# VU_LED.net
KiCad netlist of a schematic drawn in Altium Designer
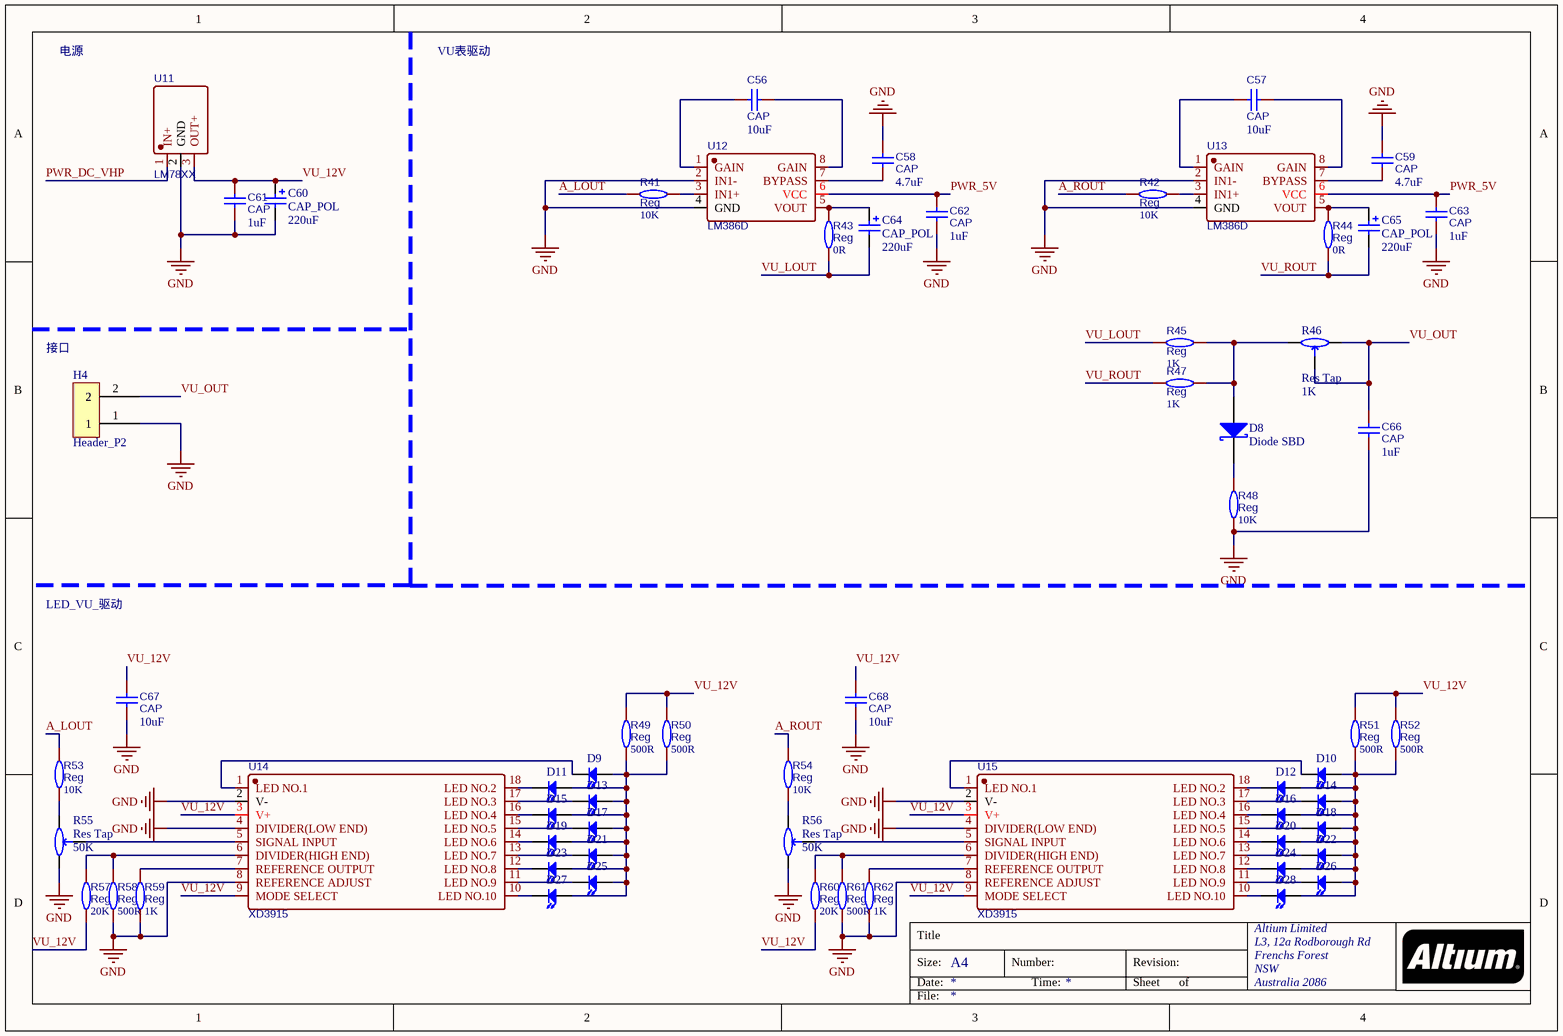
[diagram p0: VU_LED.SchDoc]

(export (version "E")
  (design (tool "Eeschema 10.0.6"))
  (components
    (comp (ref "C56")
      (value "CAP")
      (footprint "C0603")
      (description "Cap")
      (fields
        (field (name "BOM_SUPPLIER PART") "C302008")
        (field (name "BOM_MANUFACTURER PART") "0603B103K101CT")
        (field (name "ALTIUM_VALUE") "10uF")
        (field (name "CONTRIBUTOR") "LCSC")
      )
      (libsource (lib "Levent_lib") (part "CAP"))
    )
    (comp (ref "C57")
      (value "CAP")
      (footprint "C0603")
      (description "Cap")
      (fields
        (field (name "BOM_SUPPLIER PART") "C302008")
        (field (name "BOM_MANUFACTURER PART") "0603B103K101CT")
        (field (name "ALTIUM_VALUE") "10uF")
        (field (name "CONTRIBUTOR") "LCSC")
      )
      (libsource (lib "Levent_lib") (part "CAP"))
    )
    (comp (ref "C58")
      (value "CAP")
      (footprint "C0603")
      (description "Cap")
      (fields
        (field (name "BOM_SUPPLIER PART") "C302008")
        (field (name "BOM_MANUFACTURER PART") "0603B103K101CT")
        (field (name "ALTIUM_VALUE") "4.7uF")
        (field (name "CONTRIBUTOR") "LCSC")
      )
      (libsource (lib "Levent_lib") (part "CAP"))
    )
    (comp (ref "C59")
      (value "CAP")
      (footprint "C0603")
      (description "Cap")
      (fields
        (field (name "BOM_SUPPLIER PART") "C302008")
        (field (name "BOM_MANUFACTURER PART") "0603B103K101CT")
        (field (name "ALTIUM_VALUE") "4.7uF")
        (field (name "CONTRIBUTOR") "LCSC")
      )
      (libsource (lib "Levent_lib") (part "CAP"))
    )
    (comp (ref "C60")
      (value "CAP_POL")
      (footprint "CAP_SMD_6.3mm")
      (description "极性电容")
      (fields (field (name "ALTIUM_VALUE") "220uF"))
      (libsource (lib "Levent_lib") (part "CAP_POL"))
    )
    (comp (ref "C61")
      (value "CAP")
      (footprint "C0603")
      (description "Cap")
      (fields
        (field (name "BOM_SUPPLIER PART") "C302008")
        (field (name "BOM_MANUFACTURER PART") "0603B103K101CT")
        (field (name "ALTIUM_VALUE") "1uF")
        (field (name "CONTRIBUTOR") "LCSC")
      )
      (libsource (lib "Levent_lib") (part "CAP"))
    )
    (comp (ref "C62")
      (value "CAP")
      (footprint "C0603")
      (description "Cap")
      (fields
        (field (name "BOM_SUPPLIER PART") "C302008")
        (field (name "BOM_MANUFACTURER PART") "0603B103K101CT")
        (field (name "ALTIUM_VALUE") "1uF")
        (field (name "CONTRIBUTOR") "LCSC")
      )
      (libsource (lib "Levent_lib") (part "CAP"))
    )
    (comp (ref "C63")
      (value "CAP")
      (footprint "C0603")
      (description "Cap")
      (fields
        (field (name "BOM_SUPPLIER PART") "C302008")
        (field (name "BOM_MANUFACTURER PART") "0603B103K101CT")
        (field (name "ALTIUM_VALUE") "1uF")
        (field (name "CONTRIBUTOR") "LCSC")
      )
      (libsource (lib "Levent_lib") (part "CAP"))
    )
    (comp (ref "C64")
      (value "CAP_POL")
      (footprint "CAP_SMD_6.3mm")
      (description "极性电容")
      (fields (field (name "ALTIUM_VALUE") "220uF"))
      (libsource (lib "Levent_lib") (part "CAP_POL"))
    )
    (comp (ref "C65")
      (value "CAP_POL")
      (footprint "CAP_SMD_6.3mm")
      (description "极性电容")
      (fields (field (name "ALTIUM_VALUE") "220uF"))
      (libsource (lib "Levent_lib") (part "CAP_POL"))
    )
    (comp (ref "C66")
      (value "CAP")
      (footprint "C0603")
      (description "Cap")
      (fields
        (field (name "BOM_SUPPLIER PART") "C302008")
        (field (name "BOM_MANUFACTURER PART") "0603B103K101CT")
        (field (name "ALTIUM_VALUE") "1uF")
        (field (name "CONTRIBUTOR") "LCSC")
      )
      (libsource (lib "Levent_lib") (part "CAP"))
    )
    (comp (ref "C67")
      (value "CAP")
      (footprint "C0603")
      (description "Cap")
      (fields
        (field (name "BOM_SUPPLIER PART") "C302008")
        (field (name "BOM_MANUFACTURER PART") "0603B103K101CT")
        (field (name "ALTIUM_VALUE") "10uF")
        (field (name "CONTRIBUTOR") "LCSC")
      )
      (libsource (lib "Levent_lib") (part "CAP"))
    )
    (comp (ref "C68")
      (value "CAP")
      (footprint "C0603")
      (description "Cap")
      (fields
        (field (name "BOM_SUPPLIER PART") "C302008")
        (field (name "BOM_MANUFACTURER PART") "0603B103K101CT")
        (field (name "ALTIUM_VALUE") "10uF")
        (field (name "CONTRIBUTOR") "LCSC")
      )
      (libsource (lib "Levent_lib") (part "CAP"))
    )
    (comp (ref "D8")
      (value "Diode SBD")
      (footprint "SMA_L4.3")
      (description "Schottky Rectifier")
      (fields (field (name "PUBLISHER") "Altium Limited"))
      (libsource (lib "Levent_lib") (part "Diode SBD"))
    )
    (comp (ref "D9")
      (value "LED")
      (footprint "LED0603_Side")
      (fields (field (name "PUBLISHER") "Altium Limited"))
      (libsource (lib "Levent_lib") (part "LED0"))
    )
    (comp (ref "D10")
      (value "LED")
      (footprint "LED0603_Side")
      (fields (field (name "PUBLISHER") "Altium Limited"))
      (libsource (lib "Levent_lib") (part "LED0"))
    )
    (comp (ref "D11")
      (value "LED")
      (footprint "LED0603_Side")
      (fields (field (name "PUBLISHER") "Altium Limited"))
      (libsource (lib "Levent_lib") (part "LED0"))
    )
    (comp (ref "D12")
      (value "LED")
      (footprint "LED0603_Side")
      (fields (field (name "PUBLISHER") "Altium Limited"))
      (libsource (lib "Levent_lib") (part "LED0"))
    )
    (comp (ref "D13")
      (value "LED")
      (footprint "LED0603_Side")
      (fields (field (name "PUBLISHER") "Altium Limited"))
      (libsource (lib "Levent_lib") (part "LED0"))
    )
    (comp (ref "D14")
      (value "LED")
      (footprint "LED0603_Side")
      (fields (field (name "PUBLISHER") "Altium Limited"))
      (libsource (lib "Levent_lib") (part "LED0"))
    )
    (comp (ref "D15")
      (value "LED")
      (footprint "LED0603_Side")
      (fields (field (name "PUBLISHER") "Altium Limited"))
      (libsource (lib "Levent_lib") (part "LED0"))
    )
    (comp (ref "D16")
      (value "LED")
      (footprint "LED0603_Side")
      (fields (field (name "PUBLISHER") "Altium Limited"))
      (libsource (lib "Levent_lib") (part "LED0"))
    )
    (comp (ref "D17")
      (value "LED")
      (footprint "LED0603_Side")
      (fields (field (name "PUBLISHER") "Altium Limited"))
      (libsource (lib "Levent_lib") (part "LED0"))
    )
    (comp (ref "D18")
      (value "LED")
      (footprint "LED0603_Side")
      (fields (field (name "PUBLISHER") "Altium Limited"))
      (libsource (lib "Levent_lib") (part "LED0"))
    )
    (comp (ref "D19")
      (value "LED")
      (footprint "LED0603_Side")
      (fields (field (name "PUBLISHER") "Altium Limited"))
      (libsource (lib "Levent_lib") (part "LED0"))
    )
    (comp (ref "D20")
      (value "LED")
      (footprint "LED0603_Side")
      (fields (field (name "PUBLISHER") "Altium Limited"))
      (libsource (lib "Levent_lib") (part "LED0"))
    )
    (comp (ref "D21")
      (value "LED")
      (footprint "LED0603_Side")
      (fields (field (name "PUBLISHER") "Altium Limited"))
      (libsource (lib "Levent_lib") (part "LED0"))
    )
    (comp (ref "D22")
      (value "LED")
      (footprint "LED0603_Side")
      (fields (field (name "PUBLISHER") "Altium Limited"))
      (libsource (lib "Levent_lib") (part "LED0"))
    )
    (comp (ref "D23")
      (value "LED")
      (footprint "LED0603_Side")
      (fields (field (name "PUBLISHER") "Altium Limited"))
      (libsource (lib "Levent_lib") (part "LED0"))
    )
    (comp (ref "D24")
      (value "LED")
      (footprint "LED0603_Side")
      (fields (field (name "PUBLISHER") "Altium Limited"))
      (libsource (lib "Levent_lib") (part "LED0"))
    )
    (comp (ref "D25")
      (value "LED")
      (footprint "LED0603_Side")
      (fields (field (name "PUBLISHER") "Altium Limited"))
      (libsource (lib "Levent_lib") (part "LED0"))
    )
    (comp (ref "D26")
      (value "LED")
      (footprint "LED0603_Side")
      (fields (field (name "PUBLISHER") "Altium Limited"))
      (libsource (lib "Levent_lib") (part "LED0"))
    )
    (comp (ref "D27")
      (value "LED")
      (footprint "LED0603_Side")
      (fields (field (name "PUBLISHER") "Altium Limited"))
      (libsource (lib "Levent_lib") (part "LED0"))
    )
    (comp (ref "D28")
      (value "LED")
      (footprint "LED0603_Side")
      (fields (field (name "PUBLISHER") "Altium Limited"))
      (libsource (lib "Levent_lib") (part "LED0"))
    )
    (comp (ref "H4")
      (value "Header_P2")
      (footprint "H_2.54_P2")
      (description "2Pin排针")
      (libsource (lib "Levent_lib") (part "Header_P2"))
    )
    (comp (ref "R41")
      (value "Reg")
      (footprint "R0603")
      (description "电阻")
      (fields
        (field (name "BOM_SUPPLIER PART") "C465721")
        (field (name "BOM_MANUFACTURER PART") "AR03BTCX1002A")
        (field (name "ALTIUM_VALUE") "10K")
        (field (name "CONTRIBUTOR") "LCSC")
      )
      (libsource (lib "Levent_lib") (part "Res"))
    )
    (comp (ref "R42")
      (value "Reg")
      (footprint "R0603")
      (description "电阻")
      (fields
        (field (name "BOM_SUPPLIER PART") "C465721")
        (field (name "BOM_MANUFACTURER PART") "AR03BTCX1002A")
        (field (name "ALTIUM_VALUE") "10K")
        (field (name "CONTRIBUTOR") "LCSC")
      )
      (libsource (lib "Levent_lib") (part "Res"))
    )
    (comp (ref "R43")
      (value "Reg")
      (footprint "R0603")
      (description "电阻")
      (fields
        (field (name "BOM_SUPPLIER PART") "C465721")
        (field (name "BOM_MANUFACTURER PART") "AR03BTCX1002A")
        (field (name "ALTIUM_VALUE") "0R")
        (field (name "CONTRIBUTOR") "LCSC")
      )
      (libsource (lib "Levent_lib") (part "Res"))
    )
    (comp (ref "R44")
      (value "Reg")
      (footprint "R0603")
      (description "电阻")
      (fields
        (field (name "BOM_SUPPLIER PART") "C465721")
        (field (name "BOM_MANUFACTURER PART") "AR03BTCX1002A")
        (field (name "ALTIUM_VALUE") "0R")
        (field (name "CONTRIBUTOR") "LCSC")
      )
      (libsource (lib "Levent_lib") (part "Res"))
    )
    (comp (ref "R45")
      (value "Reg")
      (footprint "R0603")
      (description "电阻")
      (fields
        (field (name "BOM_SUPPLIER PART") "C465721")
        (field (name "BOM_MANUFACTURER PART") "AR03BTCX1002A")
        (field (name "ALTIUM_VALUE") "1K")
        (field (name "CONTRIBUTOR") "LCSC")
      )
      (libsource (lib "Levent_lib") (part "Res"))
    )
    (comp (ref "R46")
      (value "Res Tap")
      (footprint "RES_TAP_HOR")
      (description "可调电阻")
      (fields (field (name "ALTIUM_VALUE") "1K") (field (name "PUBLISHER") "Altium Limited"))
      (libsource (lib "Levent_lib") (part "Res Tap"))
    )
    (comp (ref "R47")
      (value "Reg")
      (footprint "R0603")
      (description "电阻")
      (fields
        (field (name "BOM_SUPPLIER PART") "C465721")
        (field (name "BOM_MANUFACTURER PART") "AR03BTCX1002A")
        (field (name "ALTIUM_VALUE") "1K")
        (field (name "CONTRIBUTOR") "LCSC")
      )
      (libsource (lib "Levent_lib") (part "Res"))
    )
    (comp (ref "R48")
      (value "Reg")
      (footprint "R0603")
      (description "电阻")
      (fields
        (field (name "BOM_SUPPLIER PART") "C465721")
        (field (name "BOM_MANUFACTURER PART") "AR03BTCX1002A")
        (field (name "ALTIUM_VALUE") "10K")
        (field (name "CONTRIBUTOR") "LCSC")
      )
      (libsource (lib "Levent_lib") (part "Res"))
    )
    (comp (ref "R49")
      (value "Reg")
      (footprint "R0603")
      (description "电阻")
      (fields
        (field (name "BOM_SUPPLIER PART") "C465721")
        (field (name "BOM_MANUFACTURER PART") "AR03BTCX1002A")
        (field (name "ALTIUM_VALUE") "500R")
        (field (name "CONTRIBUTOR") "LCSC")
      )
      (libsource (lib "Levent_lib") (part "Res"))
    )
    (comp (ref "R50")
      (value "Reg")
      (footprint "R0603")
      (description "电阻")
      (fields
        (field (name "BOM_SUPPLIER PART") "C465721")
        (field (name "BOM_MANUFACTURER PART") "AR03BTCX1002A")
        (field (name "ALTIUM_VALUE") "500R")
        (field (name "CONTRIBUTOR") "LCSC")
      )
      (libsource (lib "Levent_lib") (part "Res"))
    )
    (comp (ref "R51")
      (value "Reg")
      (footprint "R0603")
      (description "电阻")
      (fields
        (field (name "BOM_SUPPLIER PART") "C465721")
        (field (name "BOM_MANUFACTURER PART") "AR03BTCX1002A")
        (field (name "ALTIUM_VALUE") "500R")
        (field (name "CONTRIBUTOR") "LCSC")
      )
      (libsource (lib "Levent_lib") (part "Res"))
    )
    (comp (ref "R52")
      (value "Reg")
      (footprint "R0603")
      (description "电阻")
      (fields
        (field (name "BOM_SUPPLIER PART") "C465721")
        (field (name "BOM_MANUFACTURER PART") "AR03BTCX1002A")
        (field (name "ALTIUM_VALUE") "500R")
        (field (name "CONTRIBUTOR") "LCSC")
      )
      (libsource (lib "Levent_lib") (part "Res"))
    )
    (comp (ref "R53")
      (value "Reg")
      (footprint "R0603")
      (description "电阻")
      (fields
        (field (name "BOM_SUPPLIER PART") "C465721")
        (field (name "BOM_MANUFACTURER PART") "AR03BTCX1002A")
        (field (name "ALTIUM_VALUE") "10K")
        (field (name "CONTRIBUTOR") "LCSC")
      )
      (libsource (lib "Levent_lib") (part "Res"))
    )
    (comp (ref "R54")
      (value "Reg")
      (footprint "R0603")
      (description "电阻")
      (fields
        (field (name "BOM_SUPPLIER PART") "C465721")
        (field (name "BOM_MANUFACTURER PART") "AR03BTCX1002A")
        (field (name "ALTIUM_VALUE") "10K")
        (field (name "CONTRIBUTOR") "LCSC")
      )
      (libsource (lib "Levent_lib") (part "Res"))
    )
    (comp (ref "R55")
      (value "Res Tap")
      (footprint "RES_TAP_HOR")
      (description "可调电阻")
      (fields (field (name "ALTIUM_VALUE") "50K") (field (name "PUBLISHER") "Altium Limited"))
      (libsource (lib "Levent_lib") (part "Res Tap"))
    )
    (comp (ref "R56")
      (value "Res Tap")
      (footprint "RES_TAP_HOR")
      (description "可调电阻")
      (fields (field (name "ALTIUM_VALUE") "50K") (field (name "PUBLISHER") "Altium Limited"))
      (libsource (lib "Levent_lib") (part "Res Tap"))
    )
    (comp (ref "R57")
      (value "Reg")
      (footprint "R0603")
      (description "电阻")
      (fields
        (field (name "BOM_SUPPLIER PART") "C465721")
        (field (name "BOM_MANUFACTURER PART") "AR03BTCX1002A")
        (field (name "ALTIUM_VALUE") "20K")
        (field (name "CONTRIBUTOR") "LCSC")
      )
      (libsource (lib "Levent_lib") (part "Res"))
    )
    (comp (ref "R58")
      (value "Reg")
      (footprint "R0603")
      (description "电阻")
      (fields
        (field (name "BOM_SUPPLIER PART") "C465721")
        (field (name "BOM_MANUFACTURER PART") "AR03BTCX1002A")
        (field (name "ALTIUM_VALUE") "500R")
        (field (name "CONTRIBUTOR") "LCSC")
      )
      (libsource (lib "Levent_lib") (part "Res"))
    )
    (comp (ref "R59")
      (value "Reg")
      (footprint "R0603")
      (description "电阻")
      (fields
        (field (name "BOM_SUPPLIER PART") "C465721")
        (field (name "BOM_MANUFACTURER PART") "AR03BTCX1002A")
        (field (name "ALTIUM_VALUE") "1K")
        (field (name "CONTRIBUTOR") "LCSC")
      )
      (libsource (lib "Levent_lib") (part "Res"))
    )
    (comp (ref "R60")
      (value "Reg")
      (footprint "R0603")
      (description "电阻")
      (fields
        (field (name "BOM_SUPPLIER PART") "C465721")
        (field (name "BOM_MANUFACTURER PART") "AR03BTCX1002A")
        (field (name "ALTIUM_VALUE") "20K")
        (field (name "CONTRIBUTOR") "LCSC")
      )
      (libsource (lib "Levent_lib") (part "Res"))
    )
    (comp (ref "R61")
      (value "Reg")
      (footprint "R0603")
      (description "电阻")
      (fields
        (field (name "BOM_SUPPLIER PART") "C465721")
        (field (name "BOM_MANUFACTURER PART") "AR03BTCX1002A")
        (field (name "ALTIUM_VALUE") "500R")
        (field (name "CONTRIBUTOR") "LCSC")
      )
      (libsource (lib "Levent_lib") (part "Res"))
    )
    (comp (ref "R62")
      (value "Reg")
      (footprint "R0603")
      (description "电阻")
      (fields
        (field (name "BOM_SUPPLIER PART") "C465721")
        (field (name "BOM_MANUFACTURER PART") "AR03BTCX1002A")
        (field (name "ALTIUM_VALUE") "1K")
        (field (name "CONTRIBUTOR") "LCSC")
      )
      (libsource (lib "Levent_lib") (part "Res"))
    )
    (comp (ref "U11")
      (value "LM78XX")
      (footprint "TO-220-3_2.54_HOR")
      (description "三端稳压(正电压)")
      (fields
        (field (name "BOM_SUPPLIER PART") "C2902509")
        (field (name "BOM_MANUFACTURER PART") "LM7812T")
        (field (name "CONTRIBUTOR") "LCSC")
      )
      (libsource (lib "Levent_lib") (part "LM78XX"))
    )
    (comp (ref "U12")
      (value "LM386D")
      (footprint "SOP-8")
      (description "LM386")
      (fields (field (name "BOM_SUPPLIER PART") "C510560") (field (name "CONTRIBUTOR") "LCSC"))
      (libsource (lib "Levent_lib") (part "LM386D"))
    )
    (comp (ref "U13")
      (value "LM386D")
      (footprint "SOP-8")
      (description "LM386")
      (fields (field (name "BOM_SUPPLIER PART") "C510560") (field (name "CONTRIBUTOR") "LCSC"))
      (libsource (lib "Levent_lib") (part "LM386D"))
    )
    (comp (ref "U14")
      (value "XD3915")
      (footprint "DIP-18")
      (description "电平指示")
      (fields (field (name "BOM_SUPPLIER PART") "C609778") (field (name "CONTRIBUTOR") "LCSC"))
      (libsource (lib "Levent_lib") (part "LM3915"))
    )
    (comp (ref "U15")
      (value "XD3915")
      (footprint "DIP-18")
      (description "电平指示")
      (fields (field (name "BOM_SUPPLIER PART") "C609778") (field (name "CONTRIBUTOR") "LCSC"))
      (libsource (lib "Levent_lib") (part "LM3915"))
    )
  )
  (nets
    (net (code "1") (name "/A_LOUT") (class "Default")
      (node (ref "R41") (pin "2") (pinfunction "2_2") (pintype "passive"))
      (node (ref "R53") (pin "2") (pinfunction "2_2") (pintype "passive"))
    )
    (net (code "2") (name "/A_ROUT") (class "Default")
      (node (ref "R42") (pin "2") (pinfunction "2_2") (pintype "passive"))
      (node (ref "R54") (pin "2") (pinfunction "2_2") (pintype "passive"))
    )
    (net (code "3") (name "/PWR_5V") (class "Default")
      (node (ref "C62") (pin "1") (pinfunction "1_1") (pintype "passive"))
      (node (ref "C63") (pin "1") (pinfunction "1_1") (pintype "passive"))
      (node (ref "U12") (pin "6") (pinfunction "VCC_6") (pintype "passive"))
      (node (ref "U13") (pin "6") (pinfunction "VCC_6") (pintype "passive"))
    )
    (net (code "4") (name "/PWR_DC_VHP") (class "Default")
      (node (ref "U11") (pin "1") (pinfunction "IN+_1") (pintype "passive"))
    )
    (net (code "5") (name "/VU_12V") (class "Default")
      (node (ref "C60") (pin "1") (pinfunction "1_1") (pintype "passive"))
      (node (ref "C61") (pin "1") (pinfunction "1_1") (pintype "passive"))
      (node (ref "C67") (pin "1") (pinfunction "1_1") (pintype "passive"))
      (node (ref "C68") (pin "1") (pinfunction "1_1") (pintype "passive"))
      (node (ref "R49") (pin "2") (pinfunction "2_2") (pintype "passive"))
      (node (ref "R50") (pin "2") (pinfunction "2_2") (pintype "passive"))
      (node (ref "R51") (pin "2") (pinfunction "2_2") (pintype "passive"))
      (node (ref "R52") (pin "2") (pinfunction "2_2") (pintype "passive"))
      (node (ref "R57") (pin "2") (pinfunction "2_2") (pintype "passive"))
      (node (ref "R60") (pin "2") (pinfunction "2_2") (pintype "passive"))
      (node (ref "U11") (pin "3") (pinfunction "OUT+_3") (pintype "passive"))
      (node (ref "U14") (pin "3") (pinfunction "V+_3") (pintype "passive"))
      (node (ref "U14") (pin "9") (pinfunction "MODE_SELECT_9") (pintype "passive"))
      (node (ref "U15") (pin "3") (pinfunction "V+_3") (pintype "passive"))
      (node (ref "U15") (pin "9") (pinfunction "MODE_SELECT_9") (pintype "passive"))
    )
    (net (code "6") (name "/VU_LOUT") (class "Default")
      (node (ref "C64") (pin "2") (pinfunction "2_2") (pintype "passive"))
      (node (ref "R43") (pin "2") (pinfunction "2_2") (pintype "passive"))
      (node (ref "R45") (pin "2") (pinfunction "2_2") (pintype "passive"))
    )
    (net (code "7") (name "/VU_OUT") (class "Default")
      (node (ref "C66") (pin "1") (pinfunction "1_1") (pintype "passive"))
      (node (ref "H4") (pin "2") (pinfunction "2_2") (pintype "passive"))
      (node (ref "R46") (pin "1") (pinfunction "A_1") (pintype "passive"))
      (node (ref "R46") (pin "3") (pinfunction "TAP_3") (pintype "passive"))
    )
    (net (code "8") (name "/VU_ROUT") (class "Default")
      (node (ref "C65") (pin "2") (pinfunction "2_2") (pintype "passive"))
      (node (ref "R44") (pin "2") (pinfunction "2_2") (pintype "passive"))
      (node (ref "R47") (pin "2") (pinfunction "2_2") (pintype "passive"))
    )
    (net (code "9") (name "GND") (class "Default")
      (node (ref "C58") (pin "1") (pinfunction "1_1") (pintype "passive"))
      (node (ref "C59") (pin "1") (pinfunction "1_1") (pintype "passive"))
      (node (ref "C60") (pin "2") (pinfunction "2_2") (pintype "passive"))
      (node (ref "C61") (pin "2") (pinfunction "2_2") (pintype "passive"))
      (node (ref "C62") (pin "2") (pinfunction "2_2") (pintype "passive"))
      (node (ref "C63") (pin "2") (pinfunction "2_2") (pintype "passive"))
      (node (ref "C66") (pin "2") (pinfunction "2_2") (pintype "passive"))
      (node (ref "C67") (pin "2") (pinfunction "2_2") (pintype "passive"))
      (node (ref "C68") (pin "2") (pinfunction "2_2") (pintype "passive"))
      (node (ref "H4") (pin "1") (pinfunction "1_1") (pintype "passive"))
      (node (ref "R48") (pin "2") (pinfunction "2_2") (pintype "passive"))
      (node (ref "R55") (pin "2") (pinfunction "B_2") (pintype "passive"))
      (node (ref "R56") (pin "2") (pinfunction "B_2") (pintype "passive"))
      (node (ref "R58") (pin "2") (pinfunction "2_2") (pintype "passive"))
      (node (ref "R59") (pin "2") (pinfunction "2_2") (pintype "passive"))
      (node (ref "R61") (pin "2") (pinfunction "2_2") (pintype "passive"))
      (node (ref "R62") (pin "2") (pinfunction "2_2") (pintype "passive"))
      (node (ref "U11") (pin "2") (pinfunction "GND_2") (pintype "passive"))
      (node (ref "U12") (pin "2") (pinfunction "IN1-_2") (pintype "passive"))
      (node (ref "U12") (pin "4") (pinfunction "GND_4") (pintype "passive"))
      (node (ref "U13") (pin "2") (pinfunction "IN1-_2") (pintype "passive"))
      (node (ref "U13") (pin "4") (pinfunction "GND_4") (pintype "passive"))
      (node (ref "U14") (pin "2") (pinfunction "V-_2") (pintype "passive"))
      (node (ref "U14") (pin "4") (pinfunction "DIVIDER(LOW_END)_4") (pintype "passive"))
      (node (ref "U14") (pin "8") (pinfunction "REFERENCE_ADJUST_8") (pintype "passive"))
      (node (ref "U15") (pin "2") (pinfunction "V-_2") (pintype "passive"))
      (node (ref "U15") (pin "4") (pinfunction "DIVIDER(LOW_END)_4") (pintype "passive"))
      (node (ref "U15") (pin "8") (pinfunction "REFERENCE_ADJUST_8") (pintype "passive"))
    )
    (net (code "10") (name "Net-(C56-Pad1)") (class "Default")
      (node (ref "C56") (pin "1") (pinfunction "1_1") (pintype "passive"))
      (node (ref "U12") (pin "1") (pinfunction "GAIN_1") (pintype "passive"))
    )
    (net (code "11") (name "Net-(C56-Pad2)") (class "Default")
      (node (ref "C56") (pin "2") (pinfunction "2_2") (pintype "passive"))
      (node (ref "U12") (pin "8") (pinfunction "GAIN_8") (pintype "passive"))
    )
    (net (code "12") (name "Net-(C57-Pad1)") (class "Default")
      (node (ref "C57") (pin "1") (pinfunction "1_1") (pintype "passive"))
      (node (ref "U13") (pin "1") (pinfunction "GAIN_1") (pintype "passive"))
    )
    (net (code "13") (name "Net-(C57-Pad2)") (class "Default")
      (node (ref "C57") (pin "2") (pinfunction "2_2") (pintype "passive"))
      (node (ref "U13") (pin "8") (pinfunction "GAIN_8") (pintype "passive"))
    )
    (net (code "14") (name "Net-(D8-A)") (class "Default")
      (node (ref "D8") (pin "2") (pinfunction "A_2") (pintype "passive"))
      (node (ref "R45") (pin "1") (pinfunction "1_1") (pintype "passive"))
      (node (ref "R46") (pin "2") (pinfunction "B_2") (pintype "passive"))
      (node (ref "R47") (pin "1") (pinfunction "1_1") (pintype "passive"))
    )
    (net (code "15") (name "Net-(D8-K)") (class "Default")
      (node (ref "D8") (pin "1") (pinfunction "K_1") (pintype "passive"))
      (node (ref "R48") (pin "1") (pinfunction "1_1") (pintype "passive"))
    )
    (net (code "16") (name "Net-(D9-K)") (class "Default")
      (node (ref "D9") (pin "1") (pinfunction "K_1") (pintype "passive"))
      (node (ref "U14") (pin "1") (pinfunction "LED_NO.1_1") (pintype "passive"))
    )
    (net (code "17") (name "Net-(D10-A)") (class "Default")
      (node (ref "D10") (pin "2") (pinfunction "A_2") (pintype "passive"))
      (node (ref "D12") (pin "2") (pinfunction "A_2") (pintype "passive"))
      (node (ref "D14") (pin "2") (pinfunction "A_2") (pintype "passive"))
      (node (ref "D16") (pin "2") (pinfunction "A_2") (pintype "passive"))
      (node (ref "D18") (pin "2") (pinfunction "A_2") (pintype "passive"))
      (node (ref "D20") (pin "2") (pinfunction "A_2") (pintype "passive"))
      (node (ref "D22") (pin "2") (pinfunction "A_2") (pintype "passive"))
      (node (ref "D24") (pin "2") (pinfunction "A_2") (pintype "passive"))
      (node (ref "D26") (pin "2") (pinfunction "A_2") (pintype "passive"))
      (node (ref "D28") (pin "2") (pinfunction "A_2") (pintype "passive"))
      (node (ref "R51") (pin "1") (pinfunction "1_1") (pintype "passive"))
      (node (ref "R52") (pin "1") (pinfunction "1_1") (pintype "passive"))
    )
    (net (code "18") (name "Net-(D10-K)") (class "Default")
      (node (ref "D10") (pin "1") (pinfunction "K_1") (pintype "passive"))
      (node (ref "U15") (pin "1") (pinfunction "LED_NO.1_1") (pintype "passive"))
    )
    (net (code "19") (name "Net-(D11-A)") (class "Default")
      (node (ref "D11") (pin "2") (pinfunction "A_2") (pintype "passive"))
      (node (ref "D13") (pin "2") (pinfunction "A_2") (pintype "passive"))
      (node (ref "D15") (pin "2") (pinfunction "A_2") (pintype "passive"))
      (node (ref "D17") (pin "2") (pinfunction "A_2") (pintype "passive"))
      (node (ref "D19") (pin "2") (pinfunction "A_2") (pintype "passive"))
      (node (ref "D21") (pin "2") (pinfunction "A_2") (pintype "passive"))
      (node (ref "D23") (pin "2") (pinfunction "A_2") (pintype "passive"))
      (node (ref "D25") (pin "2") (pinfunction "A_2") (pintype "passive"))
      (node (ref "D27") (pin "2") (pinfunction "A_2") (pintype "passive"))
      (node (ref "D9") (pin "2") (pinfunction "A_2") (pintype "passive"))
      (node (ref "R49") (pin "1") (pinfunction "1_1") (pintype "passive"))
      (node (ref "R50") (pin "1") (pinfunction "1_1") (pintype "passive"))
    )
    (net (code "20") (name "Net-(D11-K)") (class "Default")
      (node (ref "D11") (pin "1") (pinfunction "K_1") (pintype "passive"))
      (node (ref "U14") (pin "18") (pinfunction "LED_NO.2_18") (pintype "passive"))
    )
    (net (code "21") (name "Net-(D12-K)") (class "Default")
      (node (ref "D12") (pin "1") (pinfunction "K_1") (pintype "passive"))
      (node (ref "U15") (pin "18") (pinfunction "LED_NO.2_18") (pintype "passive"))
    )
    (net (code "22") (name "Net-(D13-K)") (class "Default")
      (node (ref "D13") (pin "1") (pinfunction "K_1") (pintype "passive"))
      (node (ref "U14") (pin "17") (pinfunction "LED_NO.3_17") (pintype "passive"))
    )
    (net (code "23") (name "Net-(D14-K)") (class "Default")
      (node (ref "D14") (pin "1") (pinfunction "K_1") (pintype "passive"))
      (node (ref "U15") (pin "17") (pinfunction "LED_NO.3_17") (pintype "passive"))
    )
    (net (code "24") (name "Net-(D15-K)") (class "Default")
      (node (ref "D15") (pin "1") (pinfunction "K_1") (pintype "passive"))
      (node (ref "U14") (pin "16") (pinfunction "LED_NO.4_16") (pintype "passive"))
    )
    (net (code "25") (name "Net-(D16-K)") (class "Default")
      (node (ref "D16") (pin "1") (pinfunction "K_1") (pintype "passive"))
      (node (ref "U15") (pin "16") (pinfunction "LED_NO.4_16") (pintype "passive"))
    )
    (net (code "26") (name "Net-(D17-K)") (class "Default")
      (node (ref "D17") (pin "1") (pinfunction "K_1") (pintype "passive"))
      (node (ref "U14") (pin "15") (pinfunction "LED_NO.5_15") (pintype "passive"))
    )
    (net (code "27") (name "Net-(D18-K)") (class "Default")
      (node (ref "D18") (pin "1") (pinfunction "K_1") (pintype "passive"))
      (node (ref "U15") (pin "15") (pinfunction "LED_NO.5_15") (pintype "passive"))
    )
    (net (code "28") (name "Net-(D19-K)") (class "Default")
      (node (ref "D19") (pin "1") (pinfunction "K_1") (pintype "passive"))
      (node (ref "U14") (pin "14") (pinfunction "LED_NO.6_14") (pintype "passive"))
    )
    (net (code "29") (name "Net-(D20-K)") (class "Default")
      (node (ref "D20") (pin "1") (pinfunction "K_1") (pintype "passive"))
      (node (ref "U15") (pin "14") (pinfunction "LED_NO.6_14") (pintype "passive"))
    )
    (net (code "30") (name "Net-(D21-K)") (class "Default")
      (node (ref "D21") (pin "1") (pinfunction "K_1") (pintype "passive"))
      (node (ref "U14") (pin "13") (pinfunction "LED_NO.7_13") (pintype "passive"))
    )
    (net (code "31") (name "Net-(D22-K)") (class "Default")
      (node (ref "D22") (pin "1") (pinfunction "K_1") (pintype "passive"))
      (node (ref "U15") (pin "13") (pinfunction "LED_NO.7_13") (pintype "passive"))
    )
    (net (code "32") (name "Net-(D23-K)") (class "Default")
      (node (ref "D23") (pin "1") (pinfunction "K_1") (pintype "passive"))
      (node (ref "U14") (pin "12") (pinfunction "LED_NO.8_12") (pintype "passive"))
    )
    (net (code "33") (name "Net-(D24-K)") (class "Default")
      (node (ref "D24") (pin "1") (pinfunction "K_1") (pintype "passive"))
      (node (ref "U15") (pin "12") (pinfunction "LED_NO.8_12") (pintype "passive"))
    )
    (net (code "34") (name "Net-(D25-K)") (class "Default")
      (node (ref "D25") (pin "1") (pinfunction "K_1") (pintype "passive"))
      (node (ref "U14") (pin "11") (pinfunction "LED_NO.9_11") (pintype "passive"))
    )
    (net (code "35") (name "Net-(D26-K)") (class "Default")
      (node (ref "D26") (pin "1") (pinfunction "K_1") (pintype "passive"))
      (node (ref "U15") (pin "11") (pinfunction "LED_NO.9_11") (pintype "passive"))
    )
    (net (code "36") (name "Net-(D27-K)") (class "Default")
      (node (ref "D27") (pin "1") (pinfunction "K_1") (pintype "passive"))
      (node (ref "U14") (pin "10") (pinfunction "LED_NO.10_10") (pintype "passive"))
    )
    (net (code "37") (name "Net-(D28-K)") (class "Default")
      (node (ref "D28") (pin "1") (pinfunction "K_1") (pintype "passive"))
      (node (ref "U15") (pin "10") (pinfunction "LED_NO.10_10") (pintype "passive"))
    )
    (net (code "38") (name "Net-(R55-A)") (class "Default")
      (node (ref "R53") (pin "1") (pinfunction "1_1") (pintype "passive"))
      (node (ref "R55") (pin "1") (pinfunction "A_1") (pintype "passive"))
    )
    (net (code "39") (name "Net-(R55-TAP)") (class "Default")
      (node (ref "R55") (pin "3") (pinfunction "TAP_3") (pintype "passive"))
      (node (ref "U14") (pin "5") (pinfunction "SIGNAL_INPUT_5") (pintype "passive"))
    )
    (net (code "40") (name "Net-(R56-A)") (class "Default")
      (node (ref "R54") (pin "1") (pinfunction "1_1") (pintype "passive"))
      (node (ref "R56") (pin "1") (pinfunction "A_1") (pintype "passive"))
    )
    (net (code "41") (name "Net-(R56-TAP)") (class "Default")
      (node (ref "R56") (pin "3") (pinfunction "TAP_3") (pintype "passive"))
      (node (ref "U15") (pin "5") (pinfunction "SIGNAL_INPUT_5") (pintype "passive"))
    )
    (net (code "42") (name "Net-(U12-BYPASS)") (class "Default")
      (node (ref "C58") (pin "2") (pinfunction "2_2") (pintype "passive"))
      (node (ref "U12") (pin "7") (pinfunction "BYPASS_7") (pintype "passive"))
    )
    (net (code "43") (name "Net-(U12-IN1+)") (class "Default")
      (node (ref "R41") (pin "1") (pinfunction "1_1") (pintype "passive"))
      (node (ref "U12") (pin "3") (pinfunction "IN1+_3") (pintype "passive"))
    )
    (net (code "44") (name "Net-(U12-VOUT)") (class "Default")
      (node (ref "C64") (pin "1") (pinfunction "1_1") (pintype "passive"))
      (node (ref "R43") (pin "1") (pinfunction "1_1") (pintype "passive"))
      (node (ref "U12") (pin "5") (pinfunction "VOUT_5") (pintype "passive"))
    )
    (net (code "45") (name "Net-(U13-BYPASS)") (class "Default")
      (node (ref "C59") (pin "2") (pinfunction "2_2") (pintype "passive"))
      (node (ref "U13") (pin "7") (pinfunction "BYPASS_7") (pintype "passive"))
    )
    (net (code "46") (name "Net-(U13-IN1+)") (class "Default")
      (node (ref "R42") (pin "1") (pinfunction "1_1") (pintype "passive"))
      (node (ref "U13") (pin "3") (pinfunction "IN1+_3") (pintype "passive"))
    )
    (net (code "47") (name "Net-(U13-VOUT)") (class "Default")
      (node (ref "C65") (pin "1") (pinfunction "1_1") (pintype "passive"))
      (node (ref "R44") (pin "1") (pinfunction "1_1") (pintype "passive"))
      (node (ref "U13") (pin "5") (pinfunction "VOUT_5") (pintype "passive"))
    )
    (net (code "48") (name "Net-(U14-DIVIDER(HIGH_END))") (class "Default")
      (node (ref "R57") (pin "1") (pinfunction "1_1") (pintype "passive"))
      (node (ref "R58") (pin "1") (pinfunction "1_1") (pintype "passive"))
      (node (ref "U14") (pin "6") (pinfunction "DIVIDER(HIGH_END)_6") (pintype "passive"))
    )
    (net (code "49") (name "Net-(U14-REFERENCE_OUTPUT)") (class "Default")
      (node (ref "R59") (pin "1") (pinfunction "1_1") (pintype "passive"))
      (node (ref "U14") (pin "7") (pinfunction "REFERENCE_OUTPUT_7") (pintype "passive"))
    )
    (net (code "50") (name "Net-(U15-DIVIDER(HIGH_END))") (class "Default")
      (node (ref "R60") (pin "1") (pinfunction "1_1") (pintype "passive"))
      (node (ref "R61") (pin "1") (pinfunction "1_1") (pintype "passive"))
      (node (ref "U15") (pin "6") (pinfunction "DIVIDER(HIGH_END)_6") (pintype "passive"))
    )
    (net (code "51") (name "Net-(U15-REFERENCE_OUTPUT)") (class "Default")
      (node (ref "R62") (pin "1") (pinfunction "1_1") (pintype "passive"))
      (node (ref "U15") (pin "7") (pinfunction "REFERENCE_OUTPUT_7") (pintype "passive"))
    )
  )
)
